# SCH_speedometer_2024-07-09.net
KiCad netlist of a schematic drawn in EasyEDA
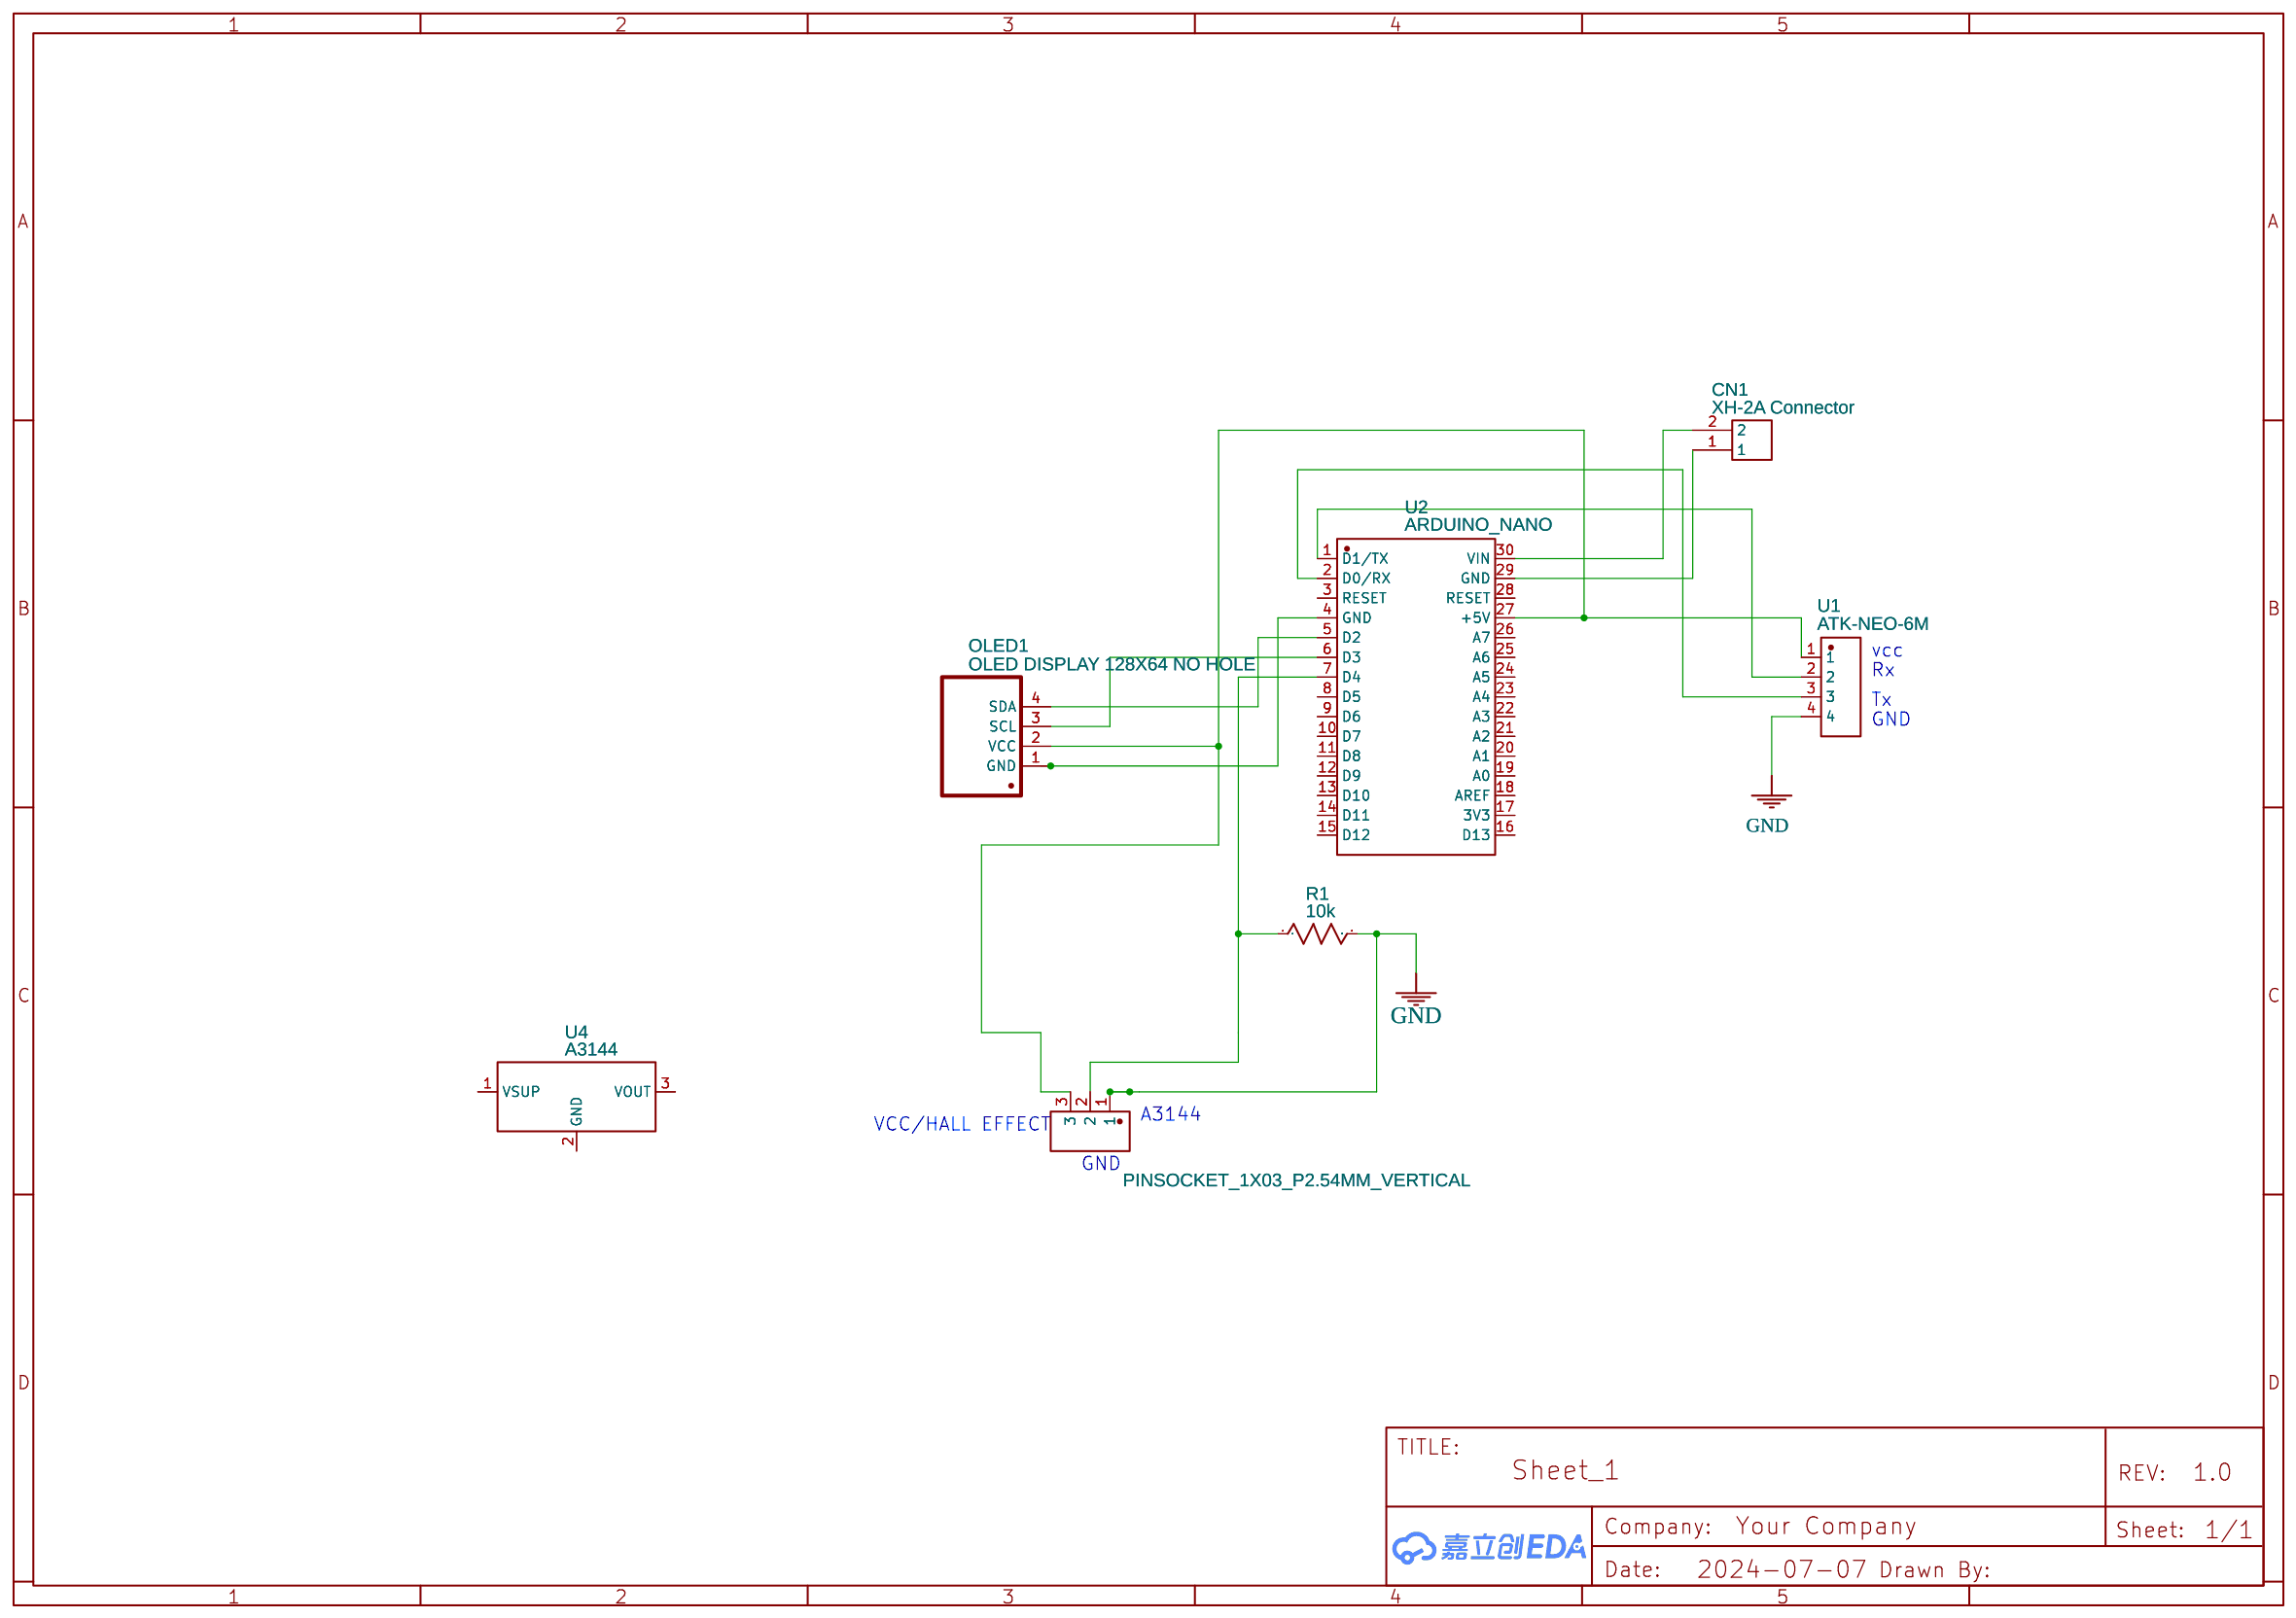
[diagram p0: schematic sheet]

(export (version "E")
  (design (tool "Eeschema 10.0.6"))
  (components
    (comp (ref "1")
      (value "PINSOCKET_1X03_P2.54MM_VERTICAL")
      (fields (field (name "Manufacturer Part") "PinSocket_1x03_P2.54mm_Vertical"))
      (libsource (lib "") (part "PINSOCKET_1X03_P2.54MM_VERTICAL"))
    )
    (comp (ref "CN1")
      (value "XH-2A Connector")
      (fields
        (field (name "BOM_Manufacturer Part") "XHB-2A Connector")
        (field (name "BOM_Supplier Part") "C57981")
      )
      (libsource (lib "") (part "XH-2A Connector"))
    )
    (comp (ref "OLED1")
      (value "OLED DISPLAY 128X64 NO HOLE")
      (libsource (lib "") (part "OLED DISPLAY 128X64 NO HOLE"))
    )
    (comp (ref "R1") (value "10k") (libsource (lib "") (part "R_0603_US")))
    (comp (ref "U1") (value "ATK-NEO-6M") (libsource (lib "") (part "ATK-NEO-6M")))
    (comp (ref "U2") (value "ARDUINO_NANO") (libsource (lib "") (part "ARDUINO_NANO")))
    (comp (ref "U4")
      (value "A3144")
      (fields (field (name "Manufacturer") "JSMSEMI(杰盛微)"))
      (libsource (lib "") (part "A3144"))
    )
  )
  (nets
    (net (code "1") (name "GND") (class "Default")
      (node (ref "1") (pin "1") (pinfunction "1_1") (pintype "unspecified"))
      (node (ref "R1") (pin "2") (pinfunction "2_2") (pintype "unspecified"))
      (node (ref "U1") (pin "4") (pinfunction "4_4") (pintype "unspecified"))
    )
    (net (code "2") (name "Net-(CN1-Pad1)") (class "Default")
      (node (ref "CN1") (pin "1") (pinfunction "1_1") (pintype "unspecified"))
      (node (ref "U2") (pin "29") (pinfunction "GND_29") (pintype "unspecified"))
    )
    (net (code "3") (name "Net-(OLED1-GND)") (class "Default")
      (node (ref "OLED1") (pin "1") (pinfunction "GND_1") (pintype "unspecified"))
      (node (ref "U2") (pin "4") (pinfunction "GND_4") (pintype "unspecified"))
    )
    (net (code "4") (name "Net-(OLED1-SCL)") (class "Default")
      (node (ref "OLED1") (pin "3") (pinfunction "SCL_3") (pintype "unspecified"))
      (node (ref "U2") (pin "6") (pinfunction "D3_6") (pintype "unspecified"))
    )
    (net (code "5") (name "Net-(OLED1-SDA)") (class "Default")
      (node (ref "OLED1") (pin "4") (pinfunction "SDA_4") (pintype "unspecified"))
      (node (ref "U2") (pin "5") (pinfunction "D2_5") (pintype "unspecified"))
    )
    (net (code "6") (name "Net-(OLED1-VCC)") (class "Default")
      (node (ref "1") (pin "3") (pinfunction "3_3") (pintype "unspecified"))
      (node (ref "OLED1") (pin "2") (pinfunction "VCC_2") (pintype "unspecified"))
      (node (ref "U1") (pin "1") (pinfunction "1_1") (pintype "unspecified"))
      (node (ref "U2") (pin "27") (pinfunction "+5V_27") (pintype "unspecified"))
    )
    (net (code "7") (name "Net-(U2-D0{slash}RX)") (class "Default")
      (node (ref "U1") (pin "3") (pinfunction "3_3") (pintype "unspecified"))
      (node (ref "U2") (pin "2") (pinfunction "D0/RX_2") (pintype "unspecified"))
    )
    (net (code "8") (name "Net-(U2-D1{slash}TX)") (class "Default")
      (node (ref "U1") (pin "2") (pinfunction "2_2") (pintype "unspecified"))
      (node (ref "U2") (pin "1") (pinfunction "D1/TX_1") (pintype "unspecified"))
    )
    (net (code "9") (name "Net-(U2-D4)") (class "Default")
      (node (ref "1") (pin "2") (pinfunction "2_2") (pintype "unspecified"))
      (node (ref "R1") (pin "1") (pinfunction "1_1") (pintype "unspecified"))
      (node (ref "U2") (pin "7") (pinfunction "D4_7") (pintype "unspecified"))
    )
    (net (code "10") (name "Net-(U2-VIN)") (class "Default")
      (node (ref "CN1") (pin "2") (pinfunction "2_2") (pintype "unspecified"))
      (node (ref "U2") (pin "30") (pinfunction "VIN_30") (pintype "unspecified"))
    )
    (net (code "11") (name "unconnected-(U2-3V3-Pad17)") (class "Default")
      (node (ref "U2") (pin "17") (pinfunction "3V3_17") (pintype "unspecified"))
    )
    (net (code "12") (name "unconnected-(U2-A0-Pad19)") (class "Default")
      (node (ref "U2") (pin "19") (pinfunction "A0_19") (pintype "unspecified"))
    )
    (net (code "13") (name "unconnected-(U2-A1-Pad20)") (class "Default")
      (node (ref "U2") (pin "20") (pinfunction "A1_20") (pintype "unspecified"))
    )
    (net (code "14") (name "unconnected-(U2-A2-Pad21)") (class "Default")
      (node (ref "U2") (pin "21") (pinfunction "A2_21") (pintype "unspecified"))
    )
    (net (code "15") (name "unconnected-(U2-A3-Pad22)") (class "Default")
      (node (ref "U2") (pin "22") (pinfunction "A3_22") (pintype "unspecified"))
    )
    (net (code "16") (name "unconnected-(U2-A4-Pad23)") (class "Default")
      (node (ref "U2") (pin "23") (pinfunction "A4_23") (pintype "unspecified"))
    )
    (net (code "17") (name "unconnected-(U2-A5-Pad24)") (class "Default")
      (node (ref "U2") (pin "24") (pinfunction "A5_24") (pintype "unspecified"))
    )
    (net (code "18") (name "unconnected-(U2-A6-Pad25)") (class "Default")
      (node (ref "U2") (pin "25") (pinfunction "A6_25") (pintype "unspecified"))
    )
    (net (code "19") (name "unconnected-(U2-A7-Pad26)") (class "Default")
      (node (ref "U2") (pin "26") (pinfunction "A7_26") (pintype "unspecified"))
    )
    (net (code "20") (name "unconnected-(U2-AREF-Pad18)") (class "Default")
      (node (ref "U2") (pin "18") (pinfunction "AREF_18") (pintype "unspecified"))
    )
    (net (code "21") (name "unconnected-(U2-D5-Pad8)") (class "Default")
      (node (ref "U2") (pin "8") (pinfunction "D5_8") (pintype "unspecified"))
    )
    (net (code "22") (name "unconnected-(U2-D6-Pad9)") (class "Default")
      (node (ref "U2") (pin "9") (pinfunction "D6_9") (pintype "unspecified"))
    )
    (net (code "23") (name "unconnected-(U2-D7-Pad10)") (class "Default")
      (node (ref "U2") (pin "10") (pinfunction "D7_10") (pintype "unspecified"))
    )
    (net (code "24") (name "unconnected-(U2-D8-Pad11)") (class "Default")
      (node (ref "U2") (pin "11") (pinfunction "D8_11") (pintype "unspecified"))
    )
    (net (code "25") (name "unconnected-(U2-D9-Pad12)") (class "Default")
      (node (ref "U2") (pin "12") (pinfunction "D9_12") (pintype "unspecified"))
    )
    (net (code "26") (name "unconnected-(U2-D10-Pad13)") (class "Default")
      (node (ref "U2") (pin "13") (pinfunction "D10_13") (pintype "unspecified"))
    )
    (net (code "27") (name "unconnected-(U2-D11-Pad14)") (class "Default")
      (node (ref "U2") (pin "14") (pinfunction "D11_14") (pintype "unspecified"))
    )
    (net (code "28") (name "unconnected-(U2-D12-Pad15)") (class "Default")
      (node (ref "U2") (pin "15") (pinfunction "D12_15") (pintype "unspecified"))
    )
    (net (code "29") (name "unconnected-(U2-D13-Pad16)") (class "Default")
      (node (ref "U2") (pin "16") (pinfunction "D13_16") (pintype "unspecified"))
    )
    (net (code "30") (name "unconnected-(U2-RESET-Pad3)") (class "Default")
      (node (ref "U2") (pin "3") (pinfunction "RESET_3") (pintype "unspecified"))
    )
    (net (code "31") (name "unconnected-(U2-RESET-Pad28)") (class "Default")
      (node (ref "U2") (pin "28") (pinfunction "RESET_28") (pintype "unspecified"))
    )
    (net (code "32") (name "unconnected-(U4-GND-Pad2)") (class "Default")
      (node (ref "U4") (pin "2") (pinfunction "GND_2") (pintype "unspecified"))
    )
    (net (code "33") (name "unconnected-(U4-VOUT-Pad3)") (class "Default")
      (node (ref "U4") (pin "3") (pinfunction "VOUT_3") (pintype "unspecified"))
    )
    (net (code "34") (name "unconnected-(U4-VSUP-Pad1)") (class "Default")
      (node (ref "U4") (pin "1") (pinfunction "VSUP_1") (pintype "unspecified"))
    )
  )
)
